# Fiber_interlock.net
KiCad netlist of a schematic drawn in Altium Designer
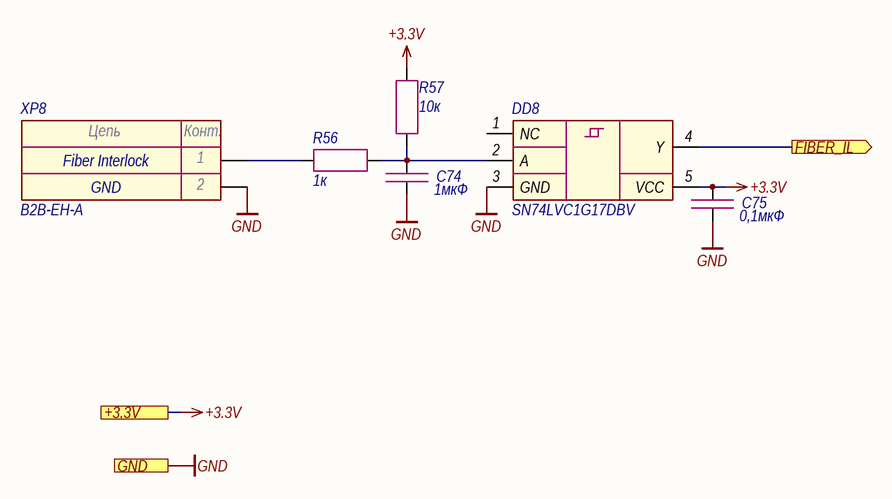
[diagram p0: Fiber_interlock.SchDoc]

(export (version "E")
  (design (tool "Eeschema 10.0.6"))
  (components
    (comp (ref "C74")
      (value "1мкФ")
      (footprint "Pcb_library:CAP_0603")
      (fields (field (name "MANUFACTURER") "Murata"))
      (libsource (lib "Schem_library") (part "Capacitor"))
    )
    (comp (ref "C75")
      (value "0,1мкФ")
      (footprint "Pcb_library:CAP_0603")
      (fields (field (name "MANUFACTURER") "Murata"))
      (libsource (lib "Schem_library") (part "Capacitor"))
    )
    (comp (ref "DD8")
      (value "SN74LVC1G17DBV")
      (footprint "Pcb_library:SOT-23-5")
      (fields (field (name "MANUFACTURER") "Texas Instruments"))
      (libsource (lib "Schem_library") (part "SN74LVC1G17"))
    )
    (comp (ref "R56")
      (value "1к")
      (footprint "Pcb_library:RES_0603")
      (fields (field (name "MANUFACTURER") "Yageo"))
      (libsource (lib "Schem_library") (part "Resistor"))
    )
    (comp (ref "R57")
      (value "10к")
      (footprint "Pcb_library:RES_0603")
      (fields (field (name "MANUFACTURER") "Yageo"))
      (libsource (lib "Schem_library") (part "Resistor"))
    )
    (comp (ref "XP8")
      (value "B2B-EH-A")
      (footprint "Pcb_library:B2B-EH-A")
      (fields (field (name "MANUFACTURER") "JST"))
      (libsource (lib "Schem_library") (part "Connector-2"))
    )
  )
  (nets
    (net (code "1") (name "+3.3V") (class "Default")
      (node (ref "C75") (pin "1") (pinfunction "1_1") (pintype "passive"))
      (node (ref "DD8") (pin "5") (pinfunction "VCC_5") (pintype "passive"))
      (node (ref "R57") (pin "2") (pinfunction "2_2") (pintype "passive"))
    )
    (net (code "2") (name "/FIBER_IL") (class "Default")
      (node (ref "DD8") (pin "4") (pinfunction "Y_4") (pintype "passive"))
    )
    (net (code "3") (name "GND") (class "Default")
      (node (ref "C74") (pin "2") (pinfunction "2_2") (pintype "passive"))
      (node (ref "C75") (pin "2") (pinfunction "2_2") (pintype "passive"))
      (node (ref "DD8") (pin "3") (pinfunction "GND_3") (pintype "passive"))
      (node (ref "XP8") (pin "2") (pintype "passive"))
    )
    (net (code "4") (name "Net-(DD8-A)") (class "Default")
      (node (ref "C74") (pin "1") (pinfunction "1_1") (pintype "passive"))
      (node (ref "DD8") (pin "2") (pinfunction "A_2") (pintype "passive"))
      (node (ref "R56") (pin "2") (pinfunction "2_2") (pintype "passive"))
      (node (ref "R57") (pin "1") (pinfunction "1_1") (pintype "passive"))
    )
    (net (code "5") (name "Net-(R56-Pad1)") (class "Default")
      (node (ref "R56") (pin "1") (pinfunction "1_1") (pintype "passive"))
      (node (ref "XP8") (pin "1") (pintype "passive"))
    )
    (net (code "6") (name "unconnected-(DD8-NC-Pad1)") (class "Default")
      (node (ref "DD8") (pin "1") (pinfunction "NC_1") (pintype "passive"))
    )
  )
)
